# UV_MONITOR.net
KiCad netlist of a schematic drawn in EAGLE
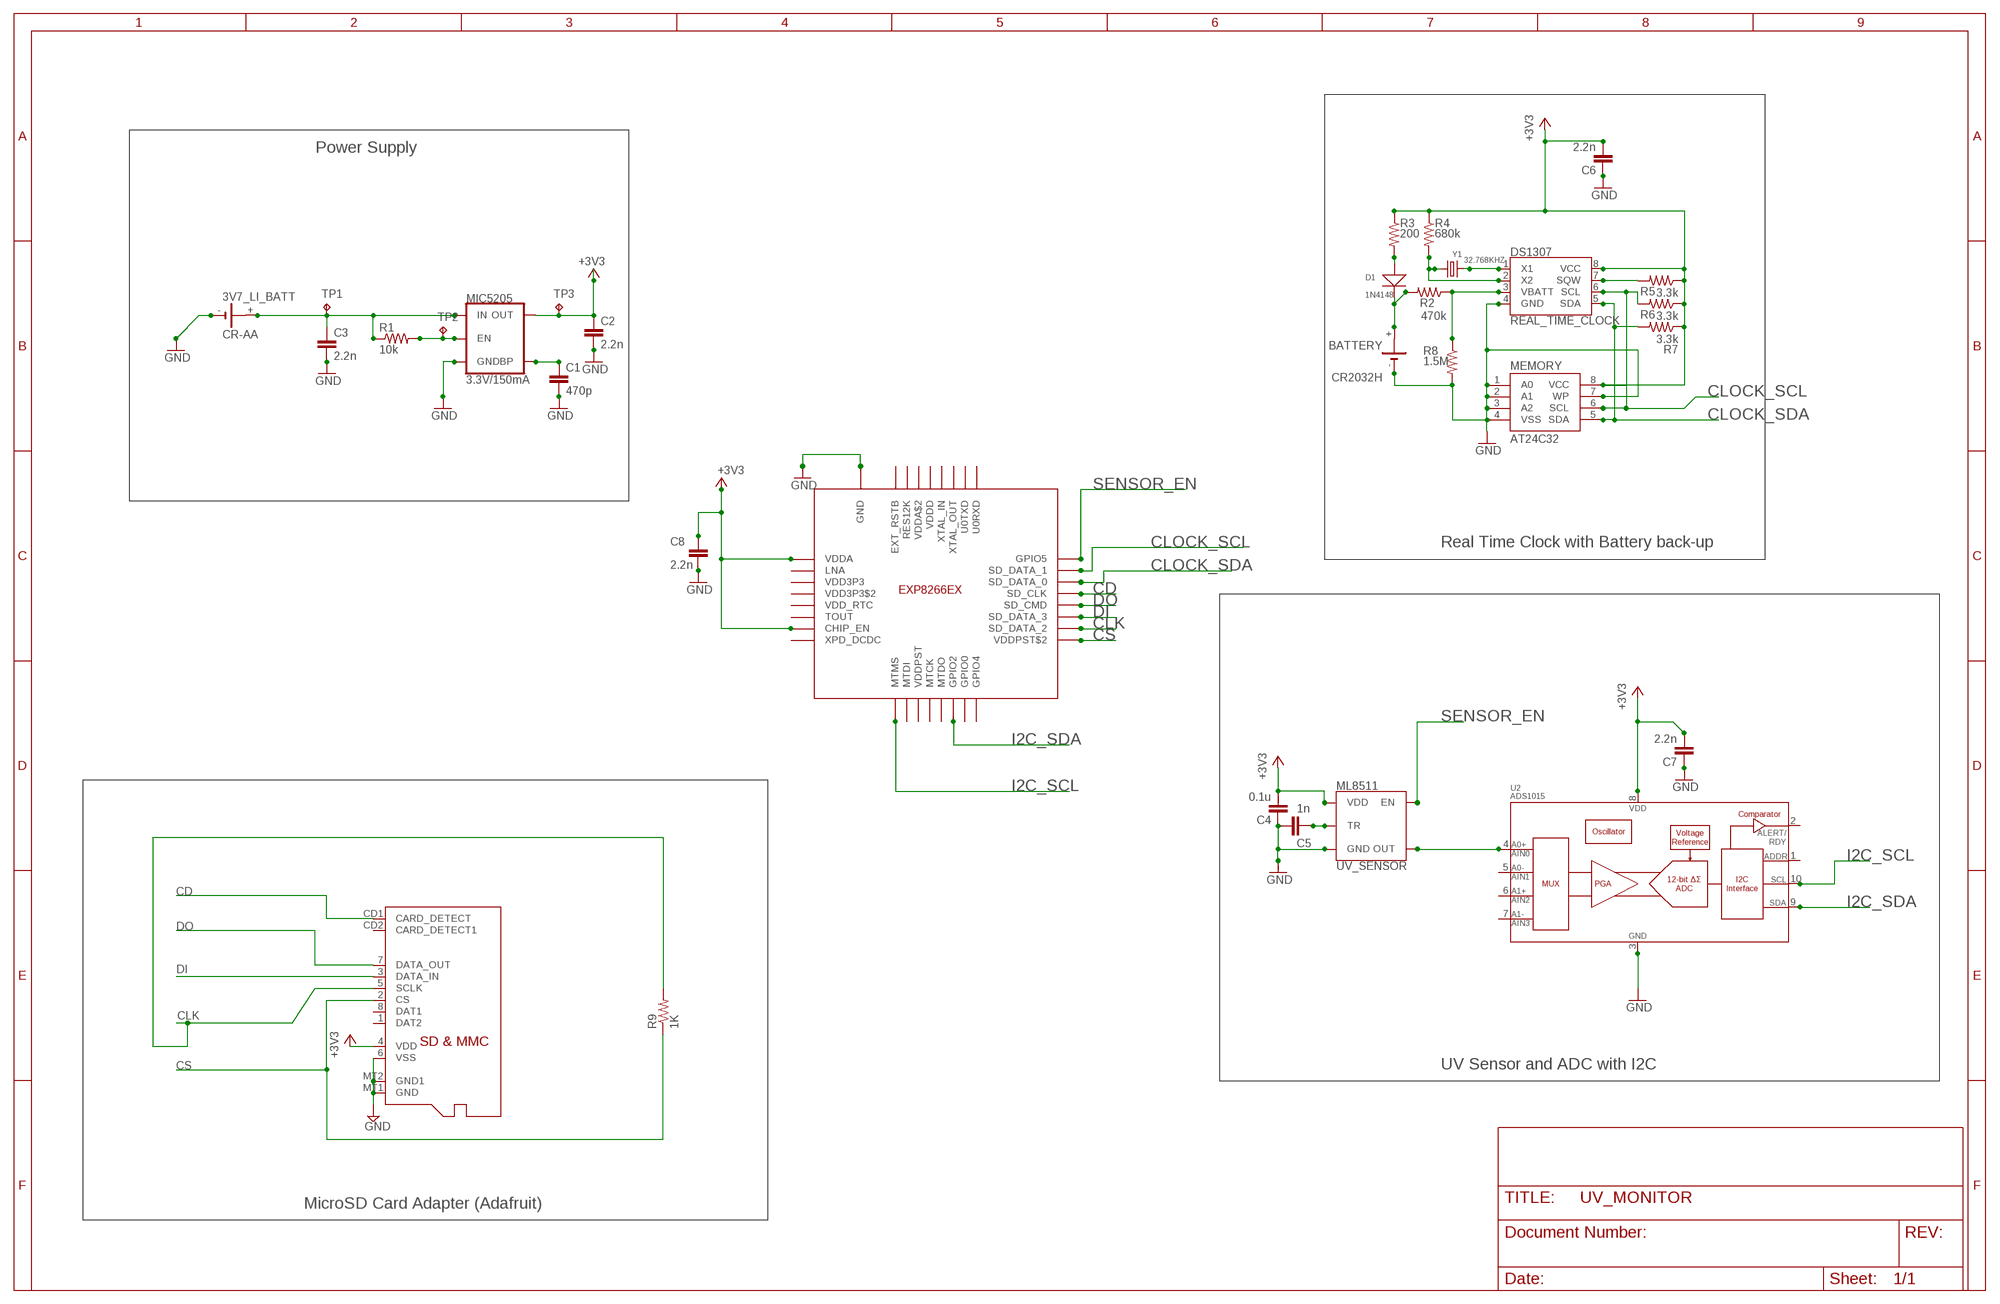
[diagram p0: schematic, sheet 1]

(export (version "E")
  (design (tool "Eeschema 10.0.6"))
  (components
    (comp (ref "3V7_LI_BATT")
      (value "CR-AA")
      (footprint "eagle-import:CRAA")
      (libsource (lib "eagle-import") (part "CR-AA"))
    )
    (comp (ref "BATTERY")
      (value "CR2032H")
      (footprint "eagle-import:CR2032H")
      (libsource (lib "eagle-import") (part "CR2032H"))
    )
    (comp (ref "C1")
      (value "470p")
      (footprint "eagle-import:C0805")
      (libsource (lib "eagle-import") (part "C-EUC0805"))
    )
    (comp (ref "C2")
      (value "2.2n")
      (footprint "eagle-import:C0805")
      (libsource (lib "eagle-import") (part "C-EUC0805"))
    )
    (comp (ref "C3")
      (value "2.2n")
      (footprint "eagle-import:C0805")
      (libsource (lib "eagle-import") (part "C-EUC0805"))
    )
    (comp (ref "C4")
      (value "0.1u")
      (footprint "eagle-import:C0805")
      (libsource (lib "eagle-import") (part "C-EUC0805"))
    )
    (comp (ref "C5")
      (value "1n")
      (footprint "eagle-import:C0805")
      (libsource (lib "eagle-import") (part "C-EUC0805"))
    )
    (comp (ref "C6")
      (value "2.2n")
      (footprint "eagle-import:C0805")
      (libsource (lib "eagle-import") (part "C-EUC0805"))
    )
    (comp (ref "C7")
      (value "2.2n")
      (footprint "eagle-import:C0805")
      (libsource (lib "eagle-import") (part "C-EUC0805"))
    )
    (comp (ref "C8")
      (value "2.2n")
      (footprint "eagle-import:C0805")
      (libsource (lib "eagle-import") (part "C-EUC0805"))
    )
    (comp (ref "D1")
      (value "1N4148")
      (footprint "eagle-import:LL-34")
      (libsource (lib "eagle-import") (part "SMD-DIODE-SWITCH-1N4148(LL-34)"))
    )
    (comp (ref "DS1307")
      (value "REAL_TIME_CLOCK")
      (footprint "eagle-import:SO08-0.15")
      (libsource (lib "eagle-import") (part "DS1307Z"))
    )
    (comp (ref "MEMORY")
      (value "AT24C32")
      (footprint "eagle-import:SO08")
      (libsource (lib "eagle-import") (part "EEPROM-I2CSMD"))
    )
    (comp (ref "MIC5205")
      (value "3.3V/150mA")
      (footprint "eagle-import:SOT23-5")
      (libsource (lib "eagle-import") (part "V_REG_MIC52053.3V"))
    )
    (comp (ref "ML8511")
      (value "UV_SENSOR")
      (footprint "eagle-import:ML8511")
      (libsource (lib "eagle-import") (part "ML8511"))
    )
    (comp (ref "R1")
      (value "10k")
      (footprint "eagle-import:R0805")
      (libsource (lib "eagle-import") (part "rcl_334_R-US_R0805"))
    )
    (comp (ref "R2")
      (value "470k")
      (footprint "eagle-import:R0805")
      (libsource (lib "eagle-import") (part "rcl_334_R-US_R0805"))
    )
    (comp (ref "R3")
      (value "200")
      (footprint "eagle-import:R0805")
      (libsource (lib "eagle-import") (part "rcl_334_R-US_R0805"))
    )
    (comp (ref "R4")
      (value "680k")
      (footprint "eagle-import:R0805")
      (libsource (lib "eagle-import") (part "rcl_334_R-US_R0805"))
    )
    (comp (ref "R5")
      (value "3.3k")
      (footprint "eagle-import:R0805")
      (libsource (lib "eagle-import") (part "rcl_334_R-US_R0805"))
    )
    (comp (ref "R6")
      (value "3.3k")
      (footprint "eagle-import:R0805")
      (libsource (lib "eagle-import") (part "rcl_334_R-US_R0805"))
    )
    (comp (ref "R7")
      (value "3.3k")
      (footprint "eagle-import:R0805")
      (libsource (lib "eagle-import") (part "rcl_334_R-US_R0805"))
    )
    (comp (ref "R8")
      (value "1.5M")
      (footprint "eagle-import:R0805")
      (libsource (lib "eagle-import") (part "rcl_334_R-US_R0805"))
    )
    (comp (ref "R9")
      (value "1K")
      (footprint "eagle-import:R0805")
      (libsource (lib "eagle-import") (part "R-US_R0805"))
    )
    (comp (ref "TP1")
      (value "TPPAD1-13")
      (footprint "eagle-import:P1-13")
      (libsource (lib "eagle-import") (part "TPPAD1-13"))
    )
    (comp (ref "TP2")
      (value "TPPAD1-13")
      (footprint "eagle-import:P1-13")
      (libsource (lib "eagle-import") (part "TPPAD1-13"))
    )
    (comp (ref "TP3")
      (value "TPPAD1-13")
      (footprint "eagle-import:P1-13")
      (libsource (lib "eagle-import") (part "TPPAD1-13"))
    )
    (comp (ref "U1")
      (value "ESP8266EX")
      (footprint "eagle-import:ESP8266EX")
      (libsource (lib "eagle-import") (part "ESP8266EX"))
    )
    (comp (ref "U2")
      (value "ADS1015")
      (footprint "eagle-import:MSOP10")
      (libsource (lib "eagle-import") (part "ADS1015"))
    )
    (comp (ref "X1")
      (value "MICROSD")
      (footprint "eagle-import:MICROSD")
      (libsource (lib "eagle-import") (part "MICROSD"))
    )
    (comp (ref "Y1")
      (value "32.768KHZ")
      (footprint "eagle-import:X2-SMD-3.2X1.5X0.55MM")
      (fields (field (name "MPN") "FC-135"))
      (libsource (lib "eagle-import") (part "SMD-CRYSTAL-ABS07-32.768KHZ-7PF-20PPM-70K(2P-3.2X1.5MM)"))
    )
  )
  (nets
    (net (code "1") (name "+3V3") (class "Default")
      (node (ref "C2") (pin "1") (pinfunction "1_1") (pintype "passive"))
      (node (ref "C4") (pin "2") (pinfunction "2_2") (pintype "passive"))
      (node (ref "C6") (pin "2") (pinfunction "2_2") (pintype "passive"))
      (node (ref "C7") (pin "2") (pinfunction "2_2") (pintype "passive"))
      (node (ref "C8") (pin "1") (pinfunction "1_1") (pintype "passive"))
      (node (ref "DS1307") (pin "8") (pinfunction "VCC_8") (pintype "bidirectional"))
      (node (ref "MEMORY") (pin "8") (pinfunction "VCC_8") (pintype "power_in"))
      (node (ref "MIC5205") (pin "5") (pinfunction "OUT_5") (pintype "passive"))
      (node (ref "ML8511") (pin "7") (pinfunction "VDD_7") (pintype "power_in"))
      (node (ref "R3") (pin "1") (pinfunction "1_1") (pintype "passive"))
      (node (ref "R4") (pin "1") (pinfunction "1_1") (pintype "passive"))
      (node (ref "R5") (pin "1") (pinfunction "1_1") (pintype "passive"))
      (node (ref "R6") (pin "1") (pinfunction "1_1") (pintype "passive"))
      (node (ref "R7") (pin "1") (pinfunction "1_1") (pintype "passive"))
      (node (ref "TP3") (pin "TP") (pinfunction "TP_TP") (pintype "input"))
      (node (ref "U1") (pin "CHIP_EN") (pinfunction "CHIP_EN_CHIP_EN") (pintype "bidirectional"))
      (node (ref "U1") (pin "VDDA") (pinfunction "VDDA_VDDA") (pintype "bidirectional"))
      (node (ref "U2") (pin "8") (pinfunction "VDD_8") (pintype "bidirectional"))
      (node (ref "X1") (pin "4") (pinfunction "VDD_4") (pintype "power_in"))
    )
    (net (code "2") (name "/CD") (class "Default")
      (node (ref "U1") (pin "SD_CLK") (pinfunction "SD_CLK_SD_CLK") (pintype "bidirectional"))
      (node (ref "X1") (pin "CD1") (pinfunction "CARD_DETECT_CD1") (pintype "passive"))
    )
    (net (code "3") (name "/CLK") (class "Default")
      (node (ref "R9") (pin "2") (pinfunction "2_2") (pintype "passive"))
      (node (ref "U1") (pin "SD_DATA_2") (pinfunction "SD_DATA_2_SD_DATA_2") (pintype "bidirectional"))
      (node (ref "X1") (pin "5") (pinfunction "SCLK_5") (pintype "input"))
    )
    (net (code "4") (name "/CLOCK_SCL") (class "Default")
      (node (ref "DS1307") (pin "6") (pinfunction "SCL_6") (pintype "bidirectional"))
      (node (ref "MEMORY") (pin "6") (pinfunction "SCL_6") (pintype "bidirectional"))
      (node (ref "R6") (pin "2") (pinfunction "2_2") (pintype "passive"))
      (node (ref "U1") (pin "SD_DATA_1") (pinfunction "SD_DATA_1_SD_DATA_1") (pintype "bidirectional"))
    )
    (net (code "5") (name "/CLOCK_SDA") (class "Default")
      (node (ref "DS1307") (pin "5") (pinfunction "SDA_5") (pintype "bidirectional"))
      (node (ref "MEMORY") (pin "5") (pinfunction "SDA_5") (pintype "bidirectional"))
      (node (ref "R7") (pin "2") (pinfunction "2_2") (pintype "passive"))
      (node (ref "U1") (pin "SD_DATA_0") (pinfunction "SD_DATA_0_SD_DATA_0") (pintype "bidirectional"))
    )
    (net (code "6") (name "/CS") (class "Default")
      (node (ref "R9") (pin "1") (pinfunction "1_1") (pintype "passive"))
      (node (ref "U1") (pin "VDDPST$2") (pinfunction "VDDPST$2_VDDPST$2") (pintype "bidirectional"))
      (node (ref "X1") (pin "2") (pinfunction "CS_2") (pintype "input"))
    )
    (net (code "7") (name "/DI") (class "Default")
      (node (ref "U1") (pin "SD_DATA_3") (pinfunction "SD_DATA_3_SD_DATA_3") (pintype "bidirectional"))
      (node (ref "X1") (pin "3") (pinfunction "DATA_IN_3") (pintype "input"))
    )
    (net (code "8") (name "/DO") (class "Default")
      (node (ref "U1") (pin "SD_CMD") (pinfunction "SD_CMD_SD_CMD") (pintype "bidirectional"))
      (node (ref "X1") (pin "7") (pinfunction "DATA_OUT_7") (pintype "output"))
    )
    (net (code "9") (name "/I2C_SCL") (class "Default")
      (node (ref "U1") (pin "MTMS") (pinfunction "MTMS_MTMS") (pintype "bidirectional"))
      (node (ref "U2") (pin "10") (pinfunction "SCL_10") (pintype "bidirectional"))
    )
    (net (code "10") (name "/I2C_SDA") (class "Default")
      (node (ref "U1") (pin "GPIO2") (pinfunction "GPIO2_GPIO2") (pintype "bidirectional"))
      (node (ref "U2") (pin "9") (pinfunction "SDA_9") (pintype "bidirectional"))
    )
    (net (code "11") (name "/SENSOR_EN") (class "Default")
      (node (ref "ML8511") (pin "4") (pinfunction "EN_4") (pintype "input"))
      (node (ref "U1") (pin "GPOIO5") (pinfunction "GPIO5_GPOIO5") (pintype "bidirectional"))
    )
    (net (code "12") (name "GND") (class "Default")
      (node (ref "3V7_LI_BATT") (pin "-") (pinfunction "-_-") (pintype "passive"))
      (node (ref "BATTERY") (pin "-") (pinfunction "-_-") (pintype "passive"))
      (node (ref "C1") (pin "2") (pinfunction "2_2") (pintype "passive"))
      (node (ref "C2") (pin "2") (pinfunction "2_2") (pintype "passive"))
      (node (ref "C3") (pin "2") (pinfunction "2_2") (pintype "passive"))
      (node (ref "C4") (pin "1") (pinfunction "1_1") (pintype "passive"))
      (node (ref "C5") (pin "2") (pinfunction "2_2") (pintype "passive"))
      (node (ref "C6") (pin "1") (pinfunction "1_1") (pintype "passive"))
      (node (ref "C7") (pin "1") (pinfunction "1_1") (pintype "passive"))
      (node (ref "C8") (pin "2") (pinfunction "2_2") (pintype "passive"))
      (node (ref "DS1307") (pin "4") (pinfunction "GND_4") (pintype "bidirectional"))
      (node (ref "MEMORY") (pin "1") (pinfunction "A0_1") (pintype "bidirectional"))
      (node (ref "MEMORY") (pin "2") (pinfunction "A1_2") (pintype "bidirectional"))
      (node (ref "MEMORY") (pin "3") (pinfunction "A2_3") (pintype "bidirectional"))
      (node (ref "MEMORY") (pin "4") (pinfunction "VSS_4") (pintype "power_in"))
      (node (ref "MEMORY") (pin "7") (pinfunction "WP_7") (pintype "bidirectional"))
      (node (ref "MIC5205") (pin "2") (pinfunction "GND_2") (pintype "input"))
      (node (ref "ML8511") (pin "5") (pinfunction "GND_5") (pintype "power_in"))
      (node (ref "R8") (pin "2") (pinfunction "2_2") (pintype "passive"))
      (node (ref "U1") (pin "GND") (pinfunction "GND_GND") (pintype "bidirectional"))
      (node (ref "U2") (pin "3") (pinfunction "VSS_3") (pintype "bidirectional"))
      (node (ref "X1") (pin "6") (pinfunction "VSS_6") (pintype "power_in"))
      (node (ref "X1") (pin "MT1") (pinfunction "GND_MT1") (pintype "power_in"))
      (node (ref "X1") (pin "MT2") (pinfunction "GND1_MT2") (pintype "power_in"))
    )
    (net (code "13") (name "Net-(D1-+)") (class "Default")
      (node (ref "D1") (pin "A") (pinfunction "+_A") (pintype "passive"))
      (node (ref "R3") (pin "2") (pinfunction "2_2") (pintype "passive"))
    )
    (net (code "14") (name "Net-(D1--)") (class "Default")
      (node (ref "BATTERY") (pin "+") (pinfunction "+_+") (pintype "passive"))
      (node (ref "D1") (pin "C") (pinfunction "-_C") (pintype "passive"))
      (node (ref "R2") (pin "2") (pinfunction "2_2") (pintype "passive"))
    )
    (net (code "15") (name "Net-(DS1307-SQW)") (class "Default")
      (node (ref "DS1307") (pin "7") (pinfunction "SQW_7") (pintype "bidirectional"))
      (node (ref "R5") (pin "2") (pinfunction "2_2") (pintype "passive"))
    )
    (net (code "16") (name "Net-(DS1307-VBATT)") (class "Default")
      (node (ref "DS1307") (pin "3") (pinfunction "VBATT_3") (pintype "bidirectional"))
      (node (ref "R2") (pin "1") (pinfunction "1_1") (pintype "passive"))
      (node (ref "R8") (pin "1") (pinfunction "1_1") (pintype "passive"))
    )
    (net (code "17") (name "Net-(DS1307-X1)") (class "Default")
      (node (ref "DS1307") (pin "1") (pinfunction "X1_1") (pintype "bidirectional"))
      (node (ref "Y1") (pin "2") (pinfunction "2_2") (pintype "passive"))
    )
    (net (code "18") (name "Net-(DS1307-X2)") (class "Default")
      (node (ref "DS1307") (pin "2") (pinfunction "X2_2") (pintype "bidirectional"))
      (node (ref "R4") (pin "2") (pinfunction "2_2") (pintype "passive"))
      (node (ref "Y1") (pin "1") (pinfunction "1_1") (pintype "passive"))
    )
    (net (code "19") (name "Net-(MIC5205-BP)") (class "Default")
      (node (ref "C1") (pin "1") (pinfunction "1_1") (pintype "passive"))
      (node (ref "MIC5205") (pin "4") (pinfunction "BP_4") (pintype "input"))
    )
    (net (code "20") (name "Net-(MIC5205-EN)") (class "Default")
      (node (ref "MIC5205") (pin "3") (pinfunction "EN_3") (pintype "input"))
      (node (ref "R1") (pin "2") (pinfunction "2_2") (pintype "passive"))
      (node (ref "TP2") (pin "TP") (pinfunction "TP_TP") (pintype "input"))
    )
    (net (code "21") (name "Net-(MIC5205-IN)") (class "Default")
      (node (ref "3V7_LI_BATT") (pin "+") (pinfunction "+_+") (pintype "passive"))
      (node (ref "C3") (pin "1") (pinfunction "1_1") (pintype "passive"))
      (node (ref "MIC5205") (pin "1") (pinfunction "IN_1") (pintype "input"))
      (node (ref "R1") (pin "1") (pinfunction "1_1") (pintype "passive"))
      (node (ref "TP1") (pin "TP") (pinfunction "TP_TP") (pintype "input"))
    )
    (net (code "22") (name "Net-(ML8511-OUT)") (class "Default")
      (node (ref "ML8511") (pin "8") (pinfunction "OUT_8") (pintype "output"))
      (node (ref "U2") (pin "4") (pinfunction "AIN0_4") (pintype "bidirectional"))
    )
    (net (code "23") (name "Net-(ML8511-TR)") (class "Default")
      (node (ref "C5") (pin "1") (pinfunction "1_1") (pintype "passive"))
      (node (ref "ML8511") (pin "10") (pinfunction "TR_10") (pintype "power_in"))
    )
    (net (code "24") (name "unconnected-(3V7_LI_BATT-+-Pad+@1)") (class "Default")
      (node (ref "3V7_LI_BATT") (pin "+@1") (pinfunction "+_+@1") (pintype "passive"))
    )
    (net (code "25") (name "unconnected-(BATTERY-+-Pad+@1)") (class "Default")
      (node (ref "BATTERY") (pin "+@1") (pinfunction "+_+@1") (pintype "passive"))
    )
    (net (code "26") (name "unconnected-(U1-PadEXT_RSTB)") (class "Default")
      (node (ref "U1") (pin "EXT_RSTB") (pinfunction "EXT_RSTB_EXT_RSTB") (pintype "bidirectional"))
    )
    (net (code "27") (name "unconnected-(U1-PadGPIO0)") (class "Default")
      (node (ref "U1") (pin "GPIO0") (pinfunction "GPIO0_GPIO0") (pintype "bidirectional"))
    )
    (net (code "28") (name "unconnected-(U1-PadGPIO4)") (class "Default")
      (node (ref "U1") (pin "GPIO4") (pinfunction "GPIO4_GPIO4") (pintype "bidirectional"))
    )
    (net (code "29") (name "unconnected-(U1-PadLNA)") (class "Default")
      (node (ref "U1") (pin "LNA") (pinfunction "LNA_LNA") (pintype "bidirectional"))
    )
    (net (code "30") (name "unconnected-(U1-PadMTCK)") (class "Default")
      (node (ref "U1") (pin "MTCK") (pinfunction "MTCK_MTCK") (pintype "bidirectional"))
    )
    (net (code "31") (name "unconnected-(U1-PadMTDI)") (class "Default")
      (node (ref "U1") (pin "MTDI") (pinfunction "MTDI_MTDI") (pintype "bidirectional"))
    )
    (net (code "32") (name "unconnected-(U1-PadMTDO)") (class "Default")
      (node (ref "U1") (pin "MTDO") (pinfunction "MTDO_MTDO") (pintype "bidirectional"))
    )
    (net (code "33") (name "unconnected-(U1-PadRES12K)") (class "Default")
      (node (ref "U1") (pin "RES12K") (pinfunction "RES12K_RES12K") (pintype "bidirectional"))
    )
    (net (code "34") (name "unconnected-(U1-PadTOUT)") (class "Default")
      (node (ref "U1") (pin "TOUT") (pinfunction "TOUT_TOUT") (pintype "bidirectional"))
    )
    (net (code "35") (name "unconnected-(U1-PadU0RXD)") (class "Default")
      (node (ref "U1") (pin "U0RXD") (pinfunction "U0RXD_U0RXD") (pintype "bidirectional"))
    )
    (net (code "36") (name "unconnected-(U1-PadU0TXD)") (class "Default")
      (node (ref "U1") (pin "U0TXD") (pinfunction "U0TXD_U0TXD") (pintype "bidirectional"))
    )
    (net (code "37") (name "unconnected-(U1-PadVDD3P3$2)") (class "Default")
      (node (ref "U1") (pin "VDD3P3$2") (pinfunction "VDD3P3$2_VDD3P3$2") (pintype "bidirectional"))
    )
    (net (code "38") (name "unconnected-(U1-PadVDD3P3)") (class "Default")
      (node (ref "U1") (pin "VDD3P3") (pinfunction "VDD3P3_VDD3P3") (pintype "bidirectional"))
    )
    (net (code "39") (name "unconnected-(U1-PadVDDA$2)") (class "Default")
      (node (ref "U1") (pin "VDDA$2") (pinfunction "VDDA$2_VDDA$2") (pintype "bidirectional"))
    )
    (net (code "40") (name "unconnected-(U1-PadVDDD)") (class "Default")
      (node (ref "U1") (pin "VDDD") (pinfunction "VDDD_VDDD") (pintype "bidirectional"))
    )
    (net (code "41") (name "unconnected-(U1-PadVDDPST)") (class "Default")
      (node (ref "U1") (pin "VDDPST") (pinfunction "VDDPST_VDDPST") (pintype "bidirectional"))
    )
    (net (code "42") (name "unconnected-(U1-PadVDD_RTC)") (class "Default")
      (node (ref "U1") (pin "VDD_RTC") (pinfunction "VDD_RTC_VDD_RTC") (pintype "bidirectional"))
    )
    (net (code "43") (name "unconnected-(U1-PadXPD_DCDC)") (class "Default")
      (node (ref "U1") (pin "XPD_DCDC") (pinfunction "XPD_DCDC_XPD_DCDC") (pintype "bidirectional"))
    )
    (net (code "44") (name "unconnected-(U1-PadXTAL_IN)") (class "Default")
      (node (ref "U1") (pin "XTAL_IN") (pinfunction "XTAL_IN_XTAL_IN") (pintype "bidirectional"))
    )
    (net (code "45") (name "unconnected-(U1-PadXTAL_OUT)") (class "Default")
      (node (ref "U1") (pin "XTAL_OUT") (pinfunction "XTAL_OUT_XTAL_OUT") (pintype "bidirectional"))
    )
    (net (code "46") (name "unconnected-(U2-ADDR-Pad1)") (class "Default")
      (node (ref "U2") (pin "1") (pinfunction "ADDR_1") (pintype "bidirectional"))
    )
    (net (code "47") (name "unconnected-(U2-AIN1-Pad5)") (class "Default")
      (node (ref "U2") (pin "5") (pinfunction "AIN1_5") (pintype "bidirectional"))
    )
    (net (code "48") (name "unconnected-(U2-AIN2-Pad6)") (class "Default")
      (node (ref "U2") (pin "6") (pinfunction "AIN2_6") (pintype "bidirectional"))
    )
    (net (code "49") (name "unconnected-(U2-AIN3-Pad7)") (class "Default")
      (node (ref "U2") (pin "7") (pinfunction "AIN3_7") (pintype "bidirectional"))
    )
    (net (code "50") (name "unconnected-(U2-ALERT{slash}RDY-Pad2)") (class "Default")
      (node (ref "U2") (pin "2") (pinfunction "ALERT/RDY_2") (pintype "bidirectional"))
    )
    (net (code "51") (name "unconnected-(X1-CARD_DETECT1-PadCD2)") (class "Default")
      (node (ref "X1") (pin "CD2") (pinfunction "CARD_DETECT1_CD2") (pintype "passive"))
    )
    (net (code "52") (name "unconnected-(X1-DAT1-Pad8)") (class "Default")
      (node (ref "X1") (pin "8") (pinfunction "DAT1_8") (pintype "bidirectional"))
    )
    (net (code "53") (name "unconnected-(X1-DAT2-Pad1)") (class "Default")
      (node (ref "X1") (pin "1") (pinfunction "DAT2_1") (pintype "bidirectional"))
    )
  )
)
